# RGB_and_TurnS.net
KiCad netlist of a schematic drawn in Altium Designer
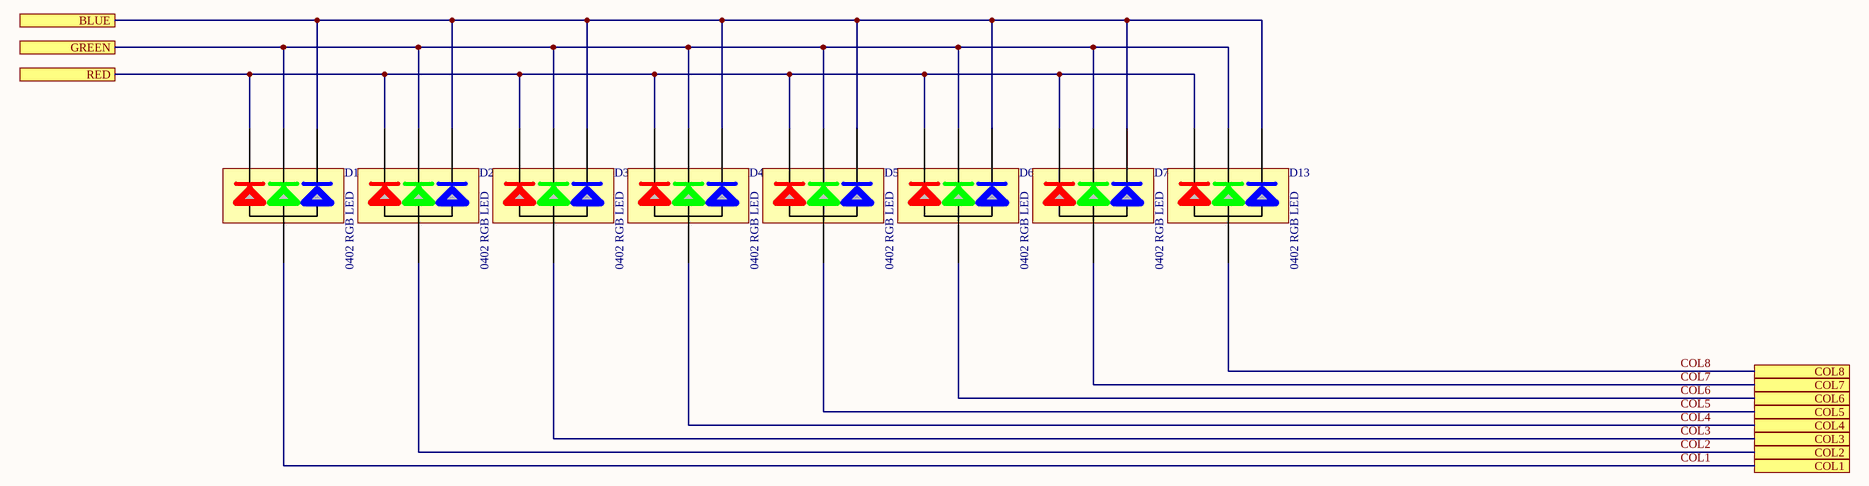
[diagram p0: RGB and TurnS.SchDoc]

(export (version "E")
  (design (tool "Eeschema 10.0.6"))
  (components
    (comp (ref "D1")
      (value "0402 RGB LED")
      (footprint "0404 RGB LED")
      (libsource (lib "Parts") (part "0402 RGB LED"))
    )
    (comp (ref "D2")
      (value "0402 RGB LED")
      (footprint "0404 RGB LED")
      (libsource (lib "Parts") (part "0402 RGB LED"))
    )
    (comp (ref "D3")
      (value "0402 RGB LED")
      (footprint "0404 RGB LED")
      (libsource (lib "Parts") (part "0402 RGB LED"))
    )
    (comp (ref "D4")
      (value "0402 RGB LED")
      (footprint "0404 RGB LED")
      (libsource (lib "Parts") (part "0402 RGB LED"))
    )
    (comp (ref "D5")
      (value "0402 RGB LED")
      (footprint "0404 RGB LED")
      (libsource (lib "Parts") (part "0402 RGB LED"))
    )
    (comp (ref "D6")
      (value "0402 RGB LED")
      (footprint "0404 RGB LED")
      (libsource (lib "Parts") (part "0402 RGB LED"))
    )
    (comp (ref "D7")
      (value "0402 RGB LED")
      (footprint "0404 RGB LED")
      (libsource (lib "Parts") (part "0402 RGB LED"))
    )
    (comp (ref "D13")
      (value "0402 RGB LED")
      (footprint "0404 RGB LED")
      (libsource (lib "Parts") (part "0402 RGB LED"))
    )
  )
  (nets
    (net (code "1") (name "/BLUE") (class "Default")
      (node (ref "D1") (pin "4") (pintype "passive"))
      (node (ref "D13") (pin "4") (pintype "passive"))
      (node (ref "D2") (pin "4") (pintype "passive"))
      (node (ref "D3") (pin "4") (pintype "passive"))
      (node (ref "D4") (pin "4") (pintype "passive"))
      (node (ref "D5") (pin "4") (pintype "passive"))
      (node (ref "D6") (pin "4") (pintype "passive"))
      (node (ref "D7") (pin "4") (pintype "passive"))
    )
    (net (code "2") (name "/COL1") (class "Default") (node (ref "D1") (pin "1") (pintype "passive")))
    (net (code "3") (name "/COL2") (class "Default") (node (ref "D2") (pin "1") (pintype "passive")))
    (net (code "4") (name "/COL3") (class "Default") (node (ref "D3") (pin "1") (pintype "passive")))
    (net (code "5") (name "/COL4") (class "Default") (node (ref "D4") (pin "1") (pintype "passive")))
    (net (code "6") (name "/COL5") (class "Default") (node (ref "D5") (pin "1") (pintype "passive")))
    (net (code "7") (name "/COL6") (class "Default") (node (ref "D6") (pin "1") (pintype "passive")))
    (net (code "8") (name "/COL7") (class "Default") (node (ref "D7") (pin "1") (pintype "passive")))
    (net (code "9") (name "/COL8") (class "Default") (node (ref "D13") (pin "1") (pintype "passive")))
    (net (code "10") (name "/GREEN") (class "Default")
      (node (ref "D1") (pin "3") (pintype "passive"))
      (node (ref "D13") (pin "3") (pintype "passive"))
      (node (ref "D2") (pin "3") (pintype "passive"))
      (node (ref "D3") (pin "3") (pintype "passive"))
      (node (ref "D4") (pin "3") (pintype "passive"))
      (node (ref "D5") (pin "3") (pintype "passive"))
      (node (ref "D6") (pin "3") (pintype "passive"))
      (node (ref "D7") (pin "3") (pintype "passive"))
    )
    (net (code "11") (name "/RED") (class "Default")
      (node (ref "D1") (pin "2") (pintype "passive"))
      (node (ref "D13") (pin "2") (pintype "passive"))
      (node (ref "D2") (pin "2") (pintype "passive"))
      (node (ref "D3") (pin "2") (pintype "passive"))
      (node (ref "D4") (pin "2") (pintype "passive"))
      (node (ref "D5") (pin "2") (pintype "passive"))
      (node (ref "D6") (pin "2") (pintype "passive"))
      (node (ref "D7") (pin "2") (pintype "passive"))
    )
  )
)
